# WS2801_MOSFET_Demo.net
KiCad netlist of a schematic drawn in EAGLE
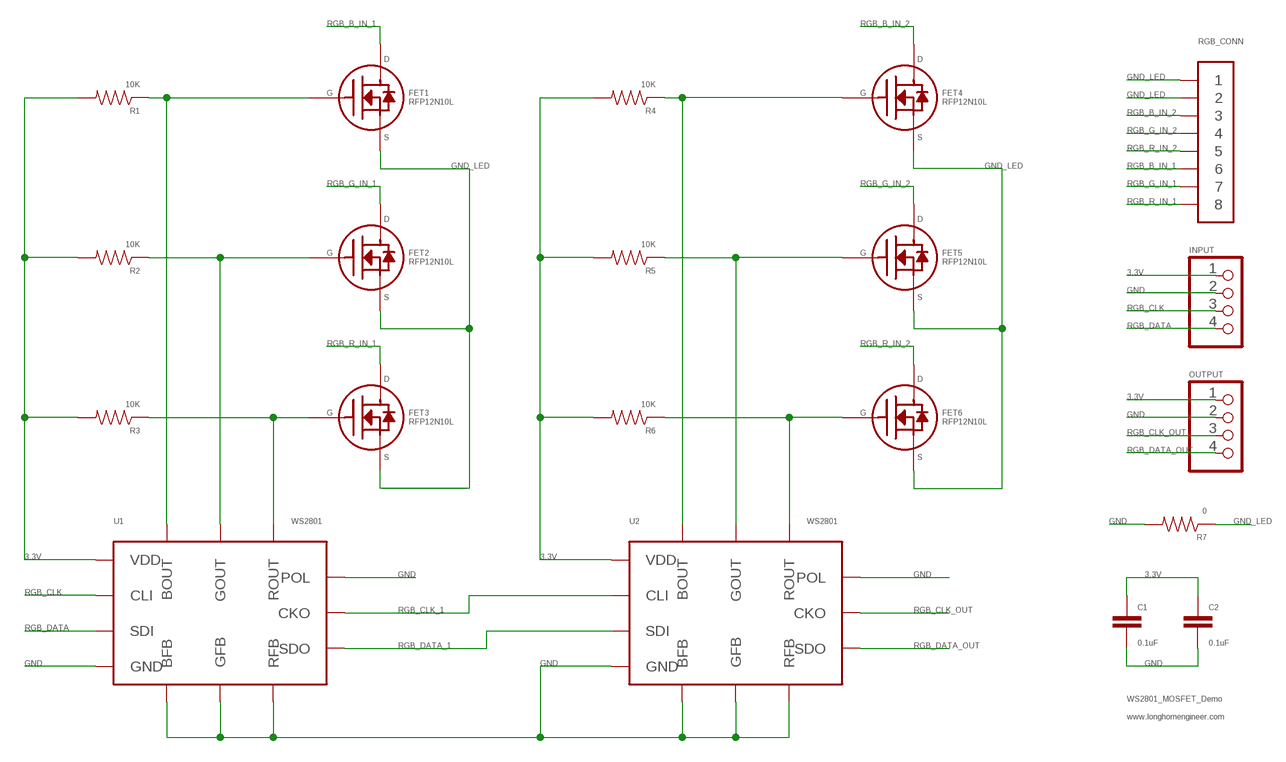
[diagram p0: schematic, sheet 1]

(export (version "E")
  (design (tool "Eeschema 10.0.6"))
  (components
    (comp (ref "C1")
      (value "0.1uF")
      (footprint "eagle-import:0402")
      (libsource (lib "eagle-import") (part "CAPACITOR_NON_POLAR0402"))
    )
    (comp (ref "C2")
      (value "0.1uF")
      (footprint "eagle-import:0402")
      (libsource (lib "eagle-import") (part "CAPACITOR_NON_POLAR0402"))
    )
    (comp (ref "FET1")
      (value "RFP12N10L")
      (footprint "eagle-import:TO-220AB")
      (libsource (lib "eagle-import") (part "MOSFET_N-CHANNEL_SINGLETO-220AB"))
    )
    (comp (ref "FET2")
      (value "RFP12N10L")
      (footprint "eagle-import:TO-220AB")
      (libsource (lib "eagle-import") (part "MOSFET_N-CHANNEL_SINGLETO-220AB"))
    )
    (comp (ref "FET3")
      (value "RFP12N10L")
      (footprint "eagle-import:TO-220AB")
      (libsource (lib "eagle-import") (part "MOSFET_N-CHANNEL_SINGLETO-220AB"))
    )
    (comp (ref "FET4")
      (value "RFP12N10L")
      (footprint "eagle-import:TO-220AB")
      (libsource (lib "eagle-import") (part "MOSFET_N-CHANNEL_SINGLETO-220AB"))
    )
    (comp (ref "FET5")
      (value "RFP12N10L")
      (footprint "eagle-import:TO-220AB")
      (libsource (lib "eagle-import") (part "MOSFET_N-CHANNEL_SINGLETO-220AB"))
    )
    (comp (ref "FET6")
      (value "RFP12N10L")
      (footprint "eagle-import:TO-220AB")
      (libsource (lib "eagle-import") (part "MOSFET_N-CHANNEL_SINGLETO-220AB"))
    )
    (comp (ref "INPUT")
      (value "PH_1X04HEADER_PTH_ROUND")
      (footprint "eagle-import:HEADER_01X04_PTH_ROUND")
      (libsource (lib "eagle-import") (part "PH_1X04HEADER_PTH_ROUND"))
    )
    (comp (ref "OUTPUT")
      (value "PH_1X04HEADER_PTH_ROUND")
      (footprint "eagle-import:HEADER_01X04_PTH_ROUND")
      (libsource (lib "eagle-import") (part "PH_1X04HEADER_PTH_ROUND"))
    )
    (comp (ref "R1")
      (value "10K")
      (footprint "eagle-import:0805")
      (libsource (lib "eagle-import") (part "RESISTOR0805"))
    )
    (comp (ref "R2")
      (value "10K")
      (footprint "eagle-import:0805")
      (libsource (lib "eagle-import") (part "RESISTOR0805"))
    )
    (comp (ref "R3")
      (value "10K")
      (footprint "eagle-import:0805")
      (libsource (lib "eagle-import") (part "RESISTOR0805"))
    )
    (comp (ref "R4")
      (value "10K")
      (footprint "eagle-import:0805")
      (libsource (lib "eagle-import") (part "RESISTOR0805"))
    )
    (comp (ref "R5")
      (value "10K")
      (footprint "eagle-import:0805")
      (libsource (lib "eagle-import") (part "RESISTOR0805"))
    )
    (comp (ref "R6")
      (value "10K")
      (footprint "eagle-import:0805")
      (libsource (lib "eagle-import") (part "RESISTOR0805"))
    )
    (comp (ref "R7")
      (value "0")
      (footprint "eagle-import:0402")
      (libsource (lib "eagle-import") (part "RESISTOR0402"))
    )
    (comp (ref "RGB_CONN")
      (value "26-60-4080")
      (footprint "eagle-import:HEADER_01X08_PTH_ROUND")
      (libsource (lib "eagle-import") (part "PH_1X08PTH_ROUND"))
    )
    (comp (ref "U1")
      (value "WS2801")
      (footprint "eagle-import:SOP-14")
      (libsource (lib "eagle-import") (part "WS2801SOP-14"))
    )
    (comp (ref "U2")
      (value "WS2801")
      (footprint "eagle-import:SOP-14")
      (libsource (lib "eagle-import") (part "WS2801SOP-14"))
    )
  )
  (nets
    (net (code "1") (name "/3.3V") (class "Default")
      (node (ref "C1") (pin "1") (pinfunction "1_1") (pintype "passive"))
      (node (ref "C2") (pin "1") (pinfunction "1_1") (pintype "passive"))
      (node (ref "INPUT") (pin "1") (pinfunction "1_1") (pintype "passive"))
      (node (ref "OUTPUT") (pin "1") (pinfunction "1_1") (pintype "passive"))
      (node (ref "R1") (pin "2") (pinfunction "2_2") (pintype "passive"))
      (node (ref "R2") (pin "2") (pinfunction "2_2") (pintype "passive"))
      (node (ref "R3") (pin "2") (pinfunction "2_2") (pintype "passive"))
      (node (ref "R4") (pin "2") (pinfunction "2_2") (pintype "passive"))
      (node (ref "R5") (pin "2") (pinfunction "2_2") (pintype "passive"))
      (node (ref "R6") (pin "2") (pinfunction "2_2") (pintype "passive"))
      (node (ref "U1") (pin "14") (pinfunction "VDD_14") (pintype "bidirectional"))
      (node (ref "U2") (pin "14") (pinfunction "VDD_14") (pintype "bidirectional"))
    )
    (net (code "2") (name "/GND") (class "Default")
      (node (ref "C1") (pin "2") (pinfunction "2_2") (pintype "passive"))
      (node (ref "C2") (pin "2") (pinfunction "2_2") (pintype "passive"))
      (node (ref "INPUT") (pin "2") (pinfunction "2_2") (pintype "passive"))
      (node (ref "OUTPUT") (pin "2") (pinfunction "2_2") (pintype "passive"))
      (node (ref "R7") (pin "2") (pinfunction "2_2") (pintype "passive"))
      (node (ref "U1") (pin "3") (pinfunction "POL_3") (pintype "bidirectional"))
      (node (ref "U1") (pin "4") (pinfunction "RFB_4") (pintype "bidirectional"))
      (node (ref "U1") (pin "5") (pinfunction "GFB_5") (pintype "bidirectional"))
      (node (ref "U1") (pin "6") (pinfunction "BFB_6") (pintype "bidirectional"))
      (node (ref "U1") (pin "7") (pinfunction "GND_7") (pintype "bidirectional"))
      (node (ref "U2") (pin "3") (pinfunction "POL_3") (pintype "bidirectional"))
      (node (ref "U2") (pin "4") (pinfunction "RFB_4") (pintype "bidirectional"))
      (node (ref "U2") (pin "5") (pinfunction "GFB_5") (pintype "bidirectional"))
      (node (ref "U2") (pin "6") (pinfunction "BFB_6") (pintype "bidirectional"))
      (node (ref "U2") (pin "7") (pinfunction "GND_7") (pintype "bidirectional"))
    )
    (net (code "3") (name "/GND_LED") (class "Default")
      (node (ref "FET1") (pin "S") (pinfunction "SOURCE_S") (pintype "bidirectional"))
      (node (ref "FET2") (pin "S") (pinfunction "SOURCE_S") (pintype "bidirectional"))
      (node (ref "FET3") (pin "S") (pinfunction "SOURCE_S") (pintype "bidirectional"))
      (node (ref "FET4") (pin "S") (pinfunction "SOURCE_S") (pintype "bidirectional"))
      (node (ref "FET5") (pin "S") (pinfunction "SOURCE_S") (pintype "bidirectional"))
      (node (ref "FET6") (pin "S") (pinfunction "SOURCE_S") (pintype "bidirectional"))
      (node (ref "R7") (pin "1") (pinfunction "1_1") (pintype "passive"))
      (node (ref "RGB_CONN") (pin "1") (pinfunction "1_1") (pintype "bidirectional"))
      (node (ref "RGB_CONN") (pin "2") (pinfunction "2_2") (pintype "bidirectional"))
    )
    (net (code "4") (name "/RGB_B_IN_1") (class "Default")
      (node (ref "FET1") (pin "D") (pinfunction "DRAIN_D") (pintype "bidirectional"))
      (node (ref "RGB_CONN") (pin "6") (pinfunction "6_6") (pintype "bidirectional"))
    )
    (net (code "5") (name "/RGB_B_IN_2") (class "Default")
      (node (ref "FET4") (pin "D") (pinfunction "DRAIN_D") (pintype "bidirectional"))
      (node (ref "RGB_CONN") (pin "3") (pinfunction "3_3") (pintype "bidirectional"))
    )
    (net (code "6") (name "/RGB_CLK") (class "Default")
      (node (ref "INPUT") (pin "3") (pinfunction "3_3") (pintype "passive"))
      (node (ref "U1") (pin "1") (pinfunction "CLI_1") (pintype "bidirectional"))
    )
    (net (code "7") (name "/RGB_CLK_1") (class "Default")
      (node (ref "U1") (pin "13") (pinfunction "CKO_13") (pintype "bidirectional"))
      (node (ref "U2") (pin "1") (pinfunction "CLI_1") (pintype "bidirectional"))
    )
    (net (code "8") (name "/RGB_CLK_OUT") (class "Default")
      (node (ref "OUTPUT") (pin "3") (pinfunction "3_3") (pintype "passive"))
      (node (ref "U2") (pin "13") (pinfunction "CKO_13") (pintype "bidirectional"))
    )
    (net (code "9") (name "/RGB_DATA") (class "Default")
      (node (ref "INPUT") (pin "4") (pinfunction "4_4") (pintype "passive"))
      (node (ref "U1") (pin "2") (pinfunction "SDI_2") (pintype "bidirectional"))
    )
    (net (code "10") (name "/RGB_DATA_1") (class "Default")
      (node (ref "U1") (pin "12") (pinfunction "SDO_12") (pintype "bidirectional"))
      (node (ref "U2") (pin "2") (pinfunction "SDI_2") (pintype "bidirectional"))
    )
    (net (code "11") (name "/RGB_DATA_OUT") (class "Default")
      (node (ref "OUTPUT") (pin "4") (pinfunction "4_4") (pintype "passive"))
      (node (ref "U2") (pin "12") (pinfunction "SDO_12") (pintype "bidirectional"))
    )
    (net (code "12") (name "/RGB_G_IN_1") (class "Default")
      (node (ref "FET2") (pin "D") (pinfunction "DRAIN_D") (pintype "bidirectional"))
      (node (ref "RGB_CONN") (pin "7") (pinfunction "7_7") (pintype "bidirectional"))
    )
    (net (code "13") (name "/RGB_G_IN_2") (class "Default")
      (node (ref "FET5") (pin "D") (pinfunction "DRAIN_D") (pintype "bidirectional"))
      (node (ref "RGB_CONN") (pin "4") (pinfunction "4_4") (pintype "bidirectional"))
    )
    (net (code "14") (name "/RGB_R_IN_1") (class "Default")
      (node (ref "FET3") (pin "D") (pinfunction "DRAIN_D") (pintype "bidirectional"))
      (node (ref "RGB_CONN") (pin "8") (pinfunction "8_8") (pintype "bidirectional"))
    )
    (net (code "15") (name "/RGB_R_IN_2") (class "Default")
      (node (ref "FET6") (pin "D") (pinfunction "DRAIN_D") (pintype "bidirectional"))
      (node (ref "RGB_CONN") (pin "5") (pinfunction "5_5") (pintype "bidirectional"))
    )
    (net (code "16") (name "Net-(FET1-GATE)") (class "Default")
      (node (ref "FET1") (pin "G") (pinfunction "GATE_G") (pintype "bidirectional"))
      (node (ref "R1") (pin "1") (pinfunction "1_1") (pintype "passive"))
      (node (ref "U1") (pin "8") (pinfunction "BOUT_8") (pintype "bidirectional"))
    )
    (net (code "17") (name "Net-(FET2-GATE)") (class "Default")
      (node (ref "FET2") (pin "G") (pinfunction "GATE_G") (pintype "bidirectional"))
      (node (ref "R2") (pin "1") (pinfunction "1_1") (pintype "passive"))
      (node (ref "U1") (pin "9") (pinfunction "GOUT_9") (pintype "bidirectional"))
    )
    (net (code "18") (name "Net-(FET3-GATE)") (class "Default")
      (node (ref "FET3") (pin "G") (pinfunction "GATE_G") (pintype "bidirectional"))
      (node (ref "R3") (pin "1") (pinfunction "1_1") (pintype "passive"))
      (node (ref "U1") (pin "10") (pinfunction "ROUT_10") (pintype "bidirectional"))
    )
    (net (code "19") (name "Net-(FET4-GATE)") (class "Default")
      (node (ref "FET4") (pin "G") (pinfunction "GATE_G") (pintype "bidirectional"))
      (node (ref "R4") (pin "1") (pinfunction "1_1") (pintype "passive"))
      (node (ref "U2") (pin "8") (pinfunction "BOUT_8") (pintype "bidirectional"))
    )
    (net (code "20") (name "Net-(FET5-GATE)") (class "Default")
      (node (ref "FET5") (pin "G") (pinfunction "GATE_G") (pintype "bidirectional"))
      (node (ref "R5") (pin "1") (pinfunction "1_1") (pintype "passive"))
      (node (ref "U2") (pin "9") (pinfunction "GOUT_9") (pintype "bidirectional"))
    )
    (net (code "21") (name "Net-(FET6-GATE)") (class "Default")
      (node (ref "FET6") (pin "G") (pinfunction "GATE_G") (pintype "bidirectional"))
      (node (ref "R6") (pin "1") (pinfunction "1_1") (pintype "passive"))
      (node (ref "U2") (pin "10") (pinfunction "ROUT_10") (pintype "bidirectional"))
    )
  )
)
